# JouleThiefLamp.net
KiCad netlist of a schematic drawn in EAGLE
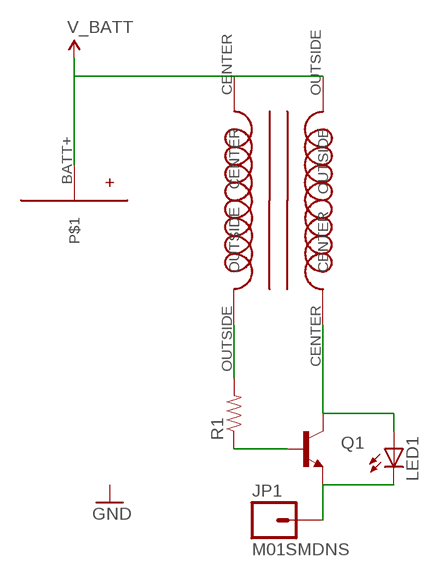
[diagram p0: schematic, sheet 1]

(export (version "E")
  (design (tool "Eeschema 10.0.6"))
  (components
    (comp (ref "JP1")
      (value "M01SMDNS")
      (footprint "eagle-import:1X01NS")
      (libsource (lib "eagle-import") (part "M01SMDNS"))
    )
    (comp (ref "LED1")
      (value "LED5MM")
      (footprint "eagle-import:LED5MM")
      (libsource (lib "eagle-import") (part "LED5MM"))
    )
    (comp (ref "Q1")
      (value "TRANSISTOR_NPNTO-92-AMMO")
      (footprint "eagle-import:TO-92-AMMO")
      (libsource (lib "eagle-import") (part "TRANSISTOR_NPNTO-92-AMMO"))
    )
    (comp (ref "R1")
      (value "RESISTORPTH-1/4W-VERT")
      (footprint "eagle-import:AXIAL-0.1")
      (libsource (lib "eagle-import") (part "RESISTORPTH-1/4W-VERT"))
    )
    (comp (ref "U$1")
      (value "AA+BATT")
      (footprint "eagle-import:AA+")
      (libsource (lib "eagle-import") (part "AA+BATT"))
    )
    (comp (ref "U$2")
      (value "HALF_CHOKE")
      (footprint "eagle-import:HALF_CHOKE")
      (libsource (lib "eagle-import") (part "HALF_CHOKE"))
    )
    (comp (ref "U$3")
      (value "HALF_CHOKE")
      (footprint "eagle-import:HALF_CHOKE")
      (libsource (lib "eagle-import") (part "HALF_CHOKE"))
    )
  )
  (nets
    (net (code "2") (name "Net-(LED1-C)") (class "Default")
      (node (ref "JP1") (pin "1") (pinfunction "1_1") (pintype "passive"))
      (node (ref "LED1") (pin "K") (pinfunction "C_K") (pintype "passive"))
      (node (ref "Q1") (pin "1") (pinfunction "E_1") (pintype "passive"))
    )
    (net (code "3") (name "Net-(Q1-B)") (class "Default")
      (node (ref "Q1") (pin "2") (pinfunction "B_2") (pintype "passive"))
      (node (ref "R1") (pin "P$1") (pinfunction "1_P$1") (pintype "passive"))
    )
    (net (code "4") (name "Net-(Q1-C)") (class "Default")
      (node (ref "LED1") (pin "A") (pinfunction "A_A") (pintype "passive"))
      (node (ref "Q1") (pin "3") (pinfunction "C_3") (pintype "passive"))
      (node (ref "U$3") (pin "CENTER") (pinfunction "CENTER_CENTER") (pintype "bidirectional"))
    )
    (net (code "5") (name "Net-(R1-2)") (class "Default")
      (node (ref "R1") (pin "P$2") (pinfunction "2_P$2") (pintype "passive"))
      (node (ref "U$3") (pin "OUTSIDE") (pinfunction "OUTSIDE_OUTSIDE") (pintype "bidirectional"))
    )
    (net (code "6") (name "V_BATT") (class "Default")
      (node (ref "U$1") (pin "BATT+") (pinfunction "P$1_BATT+") (pintype "bidirectional"))
      (node (ref "U$2") (pin "CENTER") (pinfunction "CENTER_CENTER") (pintype "bidirectional"))
      (node (ref "U$2") (pin "OUTSIDE") (pinfunction "OUTSIDE_OUTSIDE") (pintype "bidirectional"))
    )
  )
)
